# Photodiode_plate.net
KiCad netlist of a schematic drawn in EasyEDA
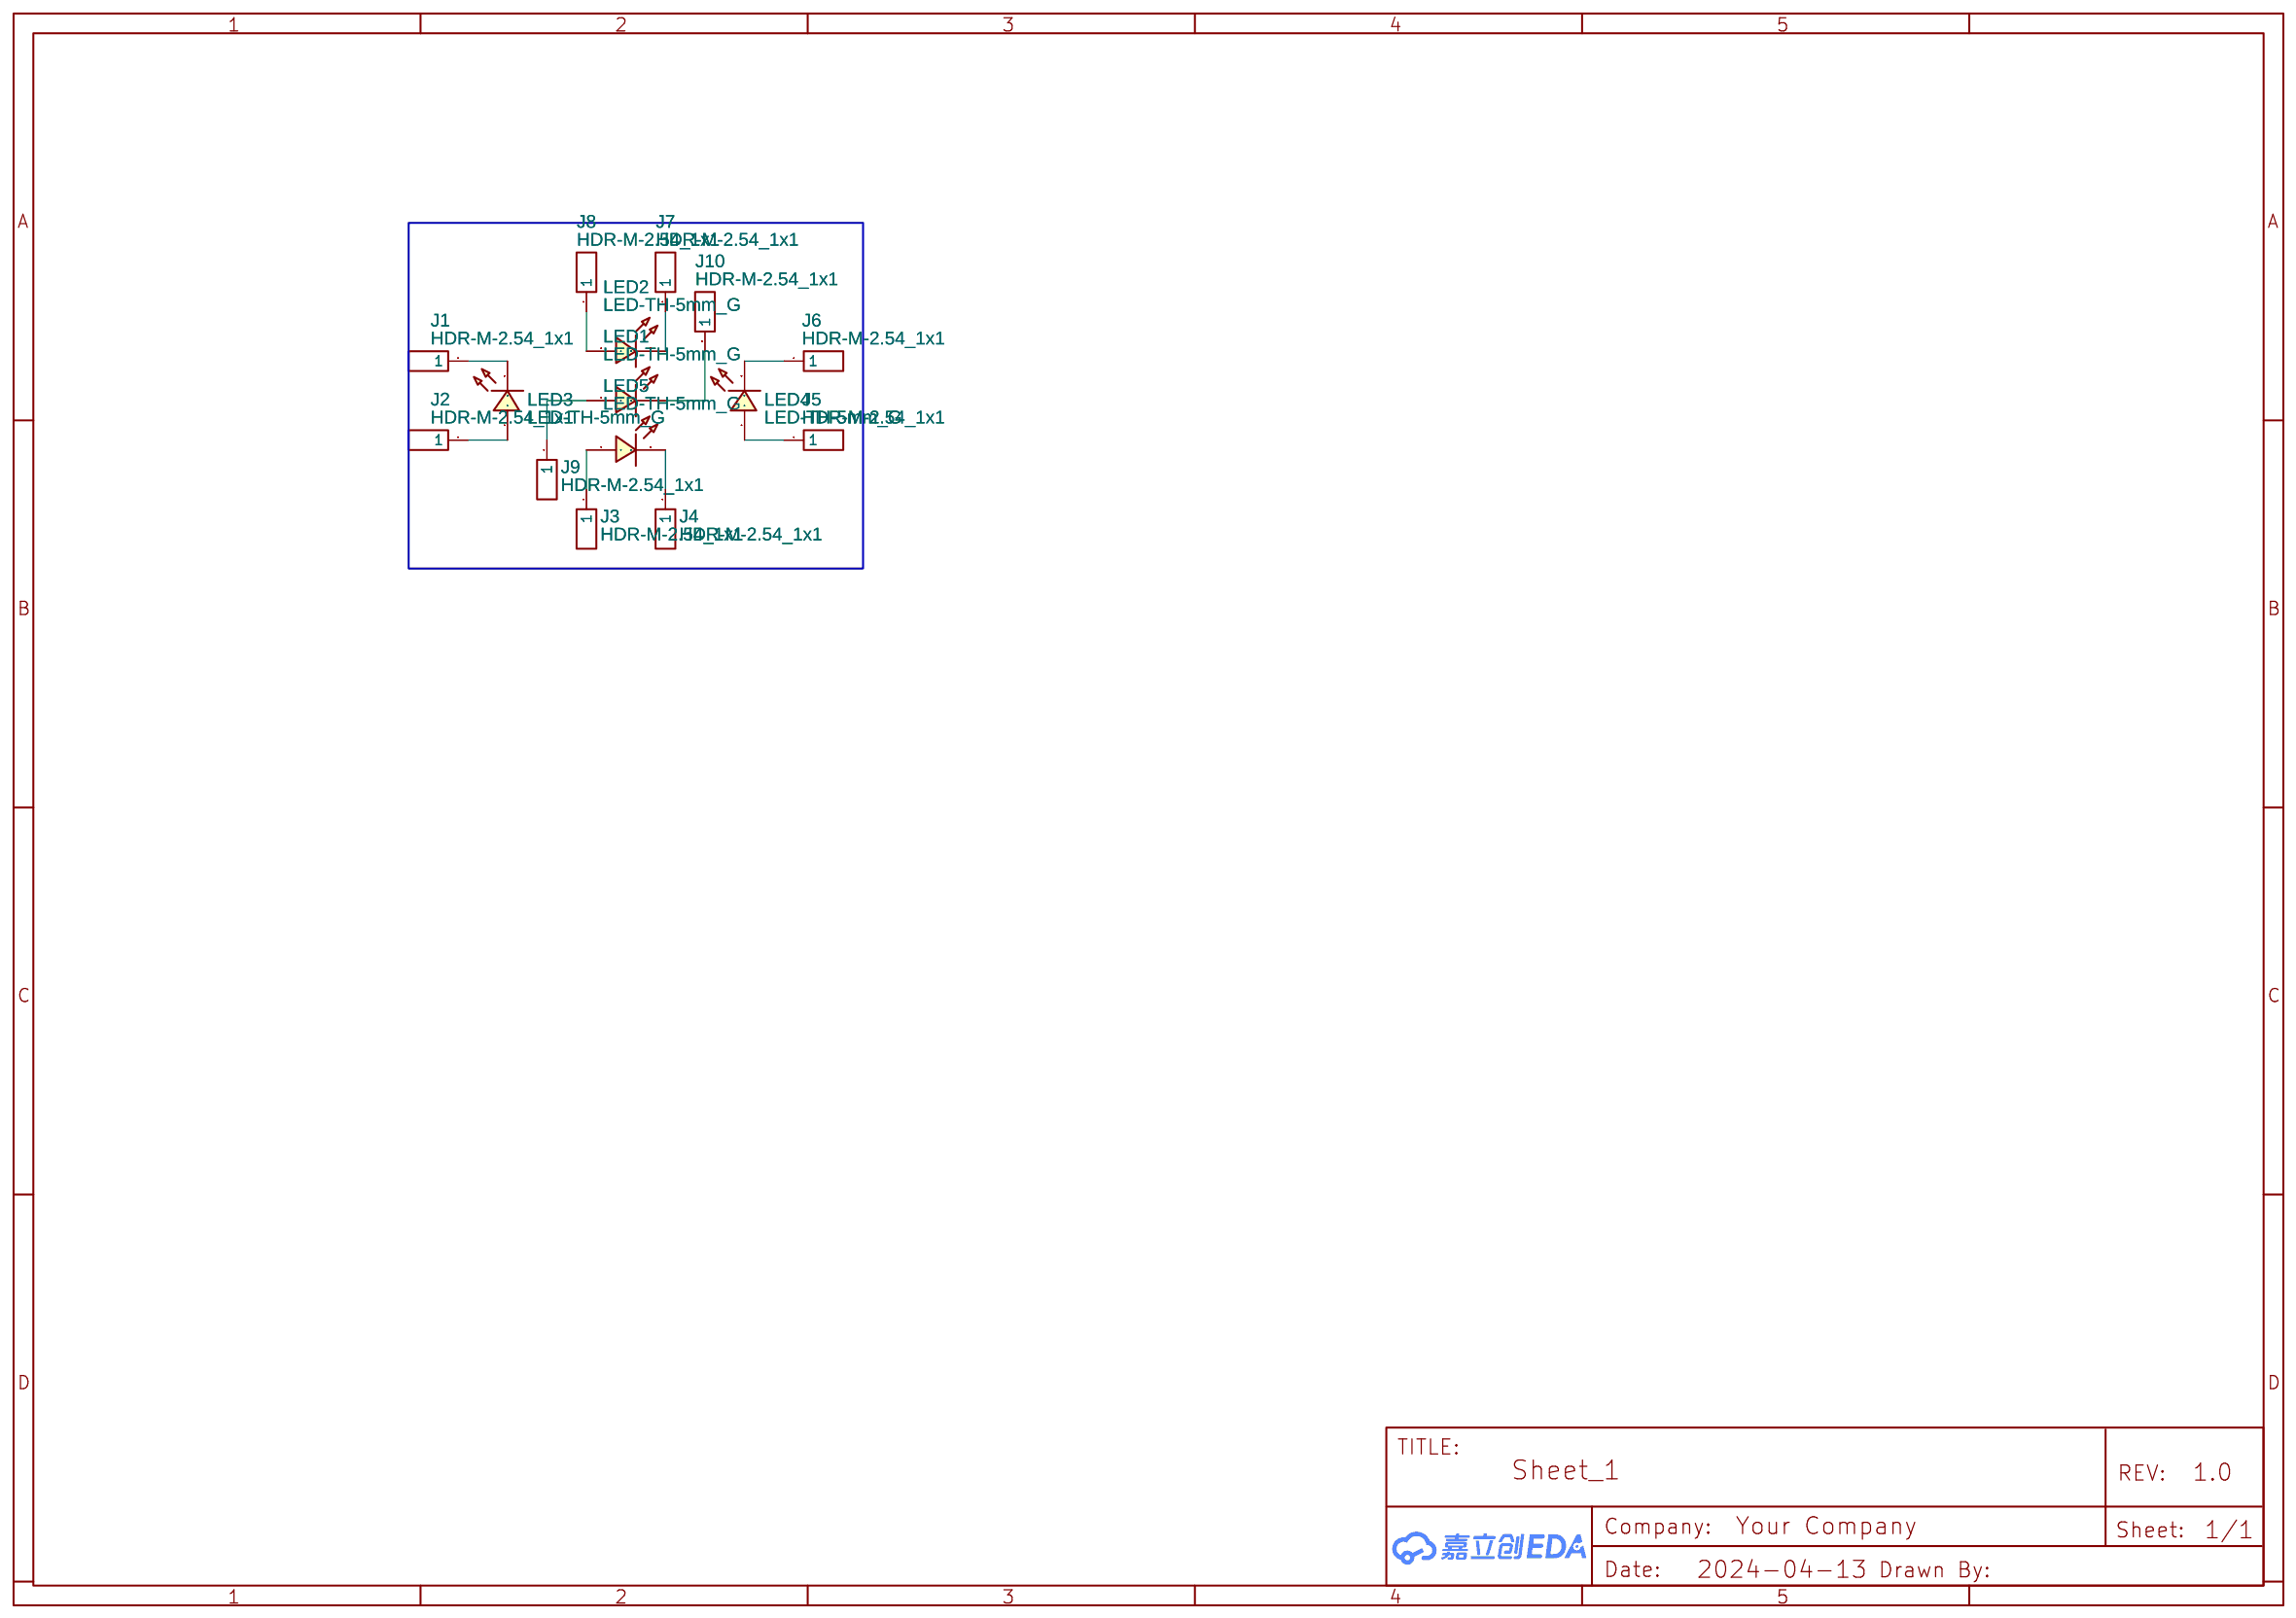
[diagram p0: schematic sheet]

(export (version "E")
  (design (tool "Eeschema 10.0.6"))
  (components
    (comp (ref "J1")
      (value "HDR-M-2.54_1x1")
      (fields (field (name "BOM_Supplier Part") "C81276"))
      (libsource (lib "") (part "HDR-M-2.54_1x1_3"))
    )
    (comp (ref "J2")
      (value "HDR-M-2.54_1x1")
      (fields (field (name "BOM_Supplier Part") "C81276"))
      (libsource (lib "") (part "HDR-M-2.54_1x1_3"))
    )
    (comp (ref "J3")
      (value "HDR-M-2.54_1x1")
      (fields (field (name "BOM_Supplier Part") "C81276"))
      (libsource (lib "") (part "HDR-M-2.54_1x1_2"))
    )
    (comp (ref "J4")
      (value "HDR-M-2.54_1x1")
      (fields (field (name "BOM_Supplier Part") "C81276"))
      (libsource (lib "") (part "HDR-M-2.54_1x1_2"))
    )
    (comp (ref "J5")
      (value "HDR-M-2.54_1x1")
      (fields (field (name "BOM_Supplier Part") "C81276"))
      (libsource (lib "") (part "HDR-M-2.54_1x1_1"))
    )
    (comp (ref "J6")
      (value "HDR-M-2.54_1x1")
      (fields (field (name "BOM_Supplier Part") "C81276"))
      (libsource (lib "") (part "HDR-M-2.54_1x1_1"))
    )
    (comp (ref "J7")
      (value "HDR-M-2.54_1x1")
      (fields (field (name "BOM_Supplier Part") "C81276"))
      (libsource (lib "") (part "HDR-M-2.54_1x1"))
    )
    (comp (ref "J8")
      (value "HDR-M-2.54_1x1")
      (fields (field (name "BOM_Supplier Part") "C81276"))
      (libsource (lib "") (part "HDR-M-2.54_1x1"))
    )
    (comp (ref "J9")
      (value "HDR-M-2.54_1x1")
      (fields (field (name "BOM_Supplier Part") "C81276"))
      (libsource (lib "") (part "HDR-M-2.54_1x1_2"))
    )
    (comp (ref "J10")
      (value "HDR-M-2.54_1x1")
      (fields (field (name "BOM_Supplier Part") "C81276"))
      (libsource (lib "") (part "HDR-M-2.54_1x1"))
    )
    (comp (ref "LED1")
      (value "LED-TH-5mm_G")
      (fields
        (field (name "BOM_Manufacturer Part") "333-2SYGD/S530-E2")
        (field (name "BOM_Supplier Part") "C88163")
      )
      (libsource (lib "") (part "LED-TH-5mm_G"))
    )
    (comp (ref "LED2")
      (value "LED-TH-5mm_G")
      (fields
        (field (name "BOM_Manufacturer Part") "333-2SYGD/S530-E2")
        (field (name "BOM_Supplier Part") "C88163")
      )
      (libsource (lib "") (part "LED-TH-5mm_G"))
    )
    (comp (ref "LED3")
      (value "LED-TH-5mm_G")
      (fields
        (field (name "BOM_Manufacturer Part") "333-2SYGD/S530-E2")
        (field (name "BOM_Supplier Part") "C88163")
      )
      (libsource (lib "") (part "LED-TH-5mm_G_1"))
    )
    (comp (ref "LED4")
      (value "LED-TH-5mm_G")
      (fields
        (field (name "BOM_Manufacturer Part") "333-2SYGD/S530-E2")
        (field (name "BOM_Supplier Part") "C88163")
      )
      (libsource (lib "") (part "LED-TH-5mm_G_1"))
    )
    (comp (ref "LED5")
      (value "LED-TH-5mm_G")
      (fields
        (field (name "BOM_Manufacturer Part") "333-2SYGD/S530-E2")
        (field (name "BOM_Supplier Part") "C88163")
      )
      (libsource (lib "") (part "LED-TH-5mm_G"))
    )
  )
  (nets
    (net (code "1") (name "Net-(J1-Pad1)") (class "Default")
      (node (ref "J1") (pin "1") (pinfunction "1_1") (pintype "input"))
      (node (ref "LED3") (pin "2") (pinfunction "2_2") (pintype "unspecified"))
    )
    (net (code "2") (name "Net-(J2-Pad1)") (class "Default")
      (node (ref "J2") (pin "1") (pinfunction "1_1") (pintype "input"))
      (node (ref "LED3") (pin "1") (pinfunction "1_1") (pintype "unspecified"))
    )
    (net (code "3") (name "Net-(J3-Pad1)") (class "Default")
      (node (ref "J3") (pin "1") (pinfunction "1_1") (pintype "input"))
      (node (ref "LED5") (pin "1") (pinfunction "1_1") (pintype "unspecified"))
    )
    (net (code "4") (name "Net-(J4-Pad1)") (class "Default")
      (node (ref "J4") (pin "1") (pinfunction "1_1") (pintype "input"))
      (node (ref "LED5") (pin "2") (pinfunction "2_2") (pintype "unspecified"))
    )
    (net (code "5") (name "Net-(J5-Pad1)") (class "Default")
      (node (ref "J5") (pin "1") (pinfunction "1_1") (pintype "input"))
      (node (ref "LED4") (pin "1") (pinfunction "1_1") (pintype "unspecified"))
    )
    (net (code "6") (name "Net-(J6-Pad1)") (class "Default")
      (node (ref "J6") (pin "1") (pinfunction "1_1") (pintype "input"))
      (node (ref "LED4") (pin "2") (pinfunction "2_2") (pintype "unspecified"))
    )
    (net (code "7") (name "Net-(J7-Pad1)") (class "Default")
      (node (ref "J7") (pin "1") (pinfunction "1_1") (pintype "input"))
      (node (ref "LED2") (pin "2") (pinfunction "2_2") (pintype "unspecified"))
    )
    (net (code "8") (name "Net-(J8-Pad1)") (class "Default")
      (node (ref "J8") (pin "1") (pinfunction "1_1") (pintype "input"))
      (node (ref "LED2") (pin "1") (pinfunction "1_1") (pintype "unspecified"))
    )
    (net (code "9") (name "Net-(J9-Pad1)") (class "Default")
      (node (ref "J9") (pin "1") (pinfunction "1_1") (pintype "input"))
      (node (ref "LED1") (pin "1") (pinfunction "1_1") (pintype "unspecified"))
    )
    (net (code "10") (name "Net-(J10-Pad1)") (class "Default")
      (node (ref "J10") (pin "1") (pinfunction "1_1") (pintype "input"))
      (node (ref "LED1") (pin "2") (pinfunction "2_2") (pintype "unspecified"))
    )
  )
)
